# EffectsBox.net
KiCad netlist of a schematic drawn in EAGLE
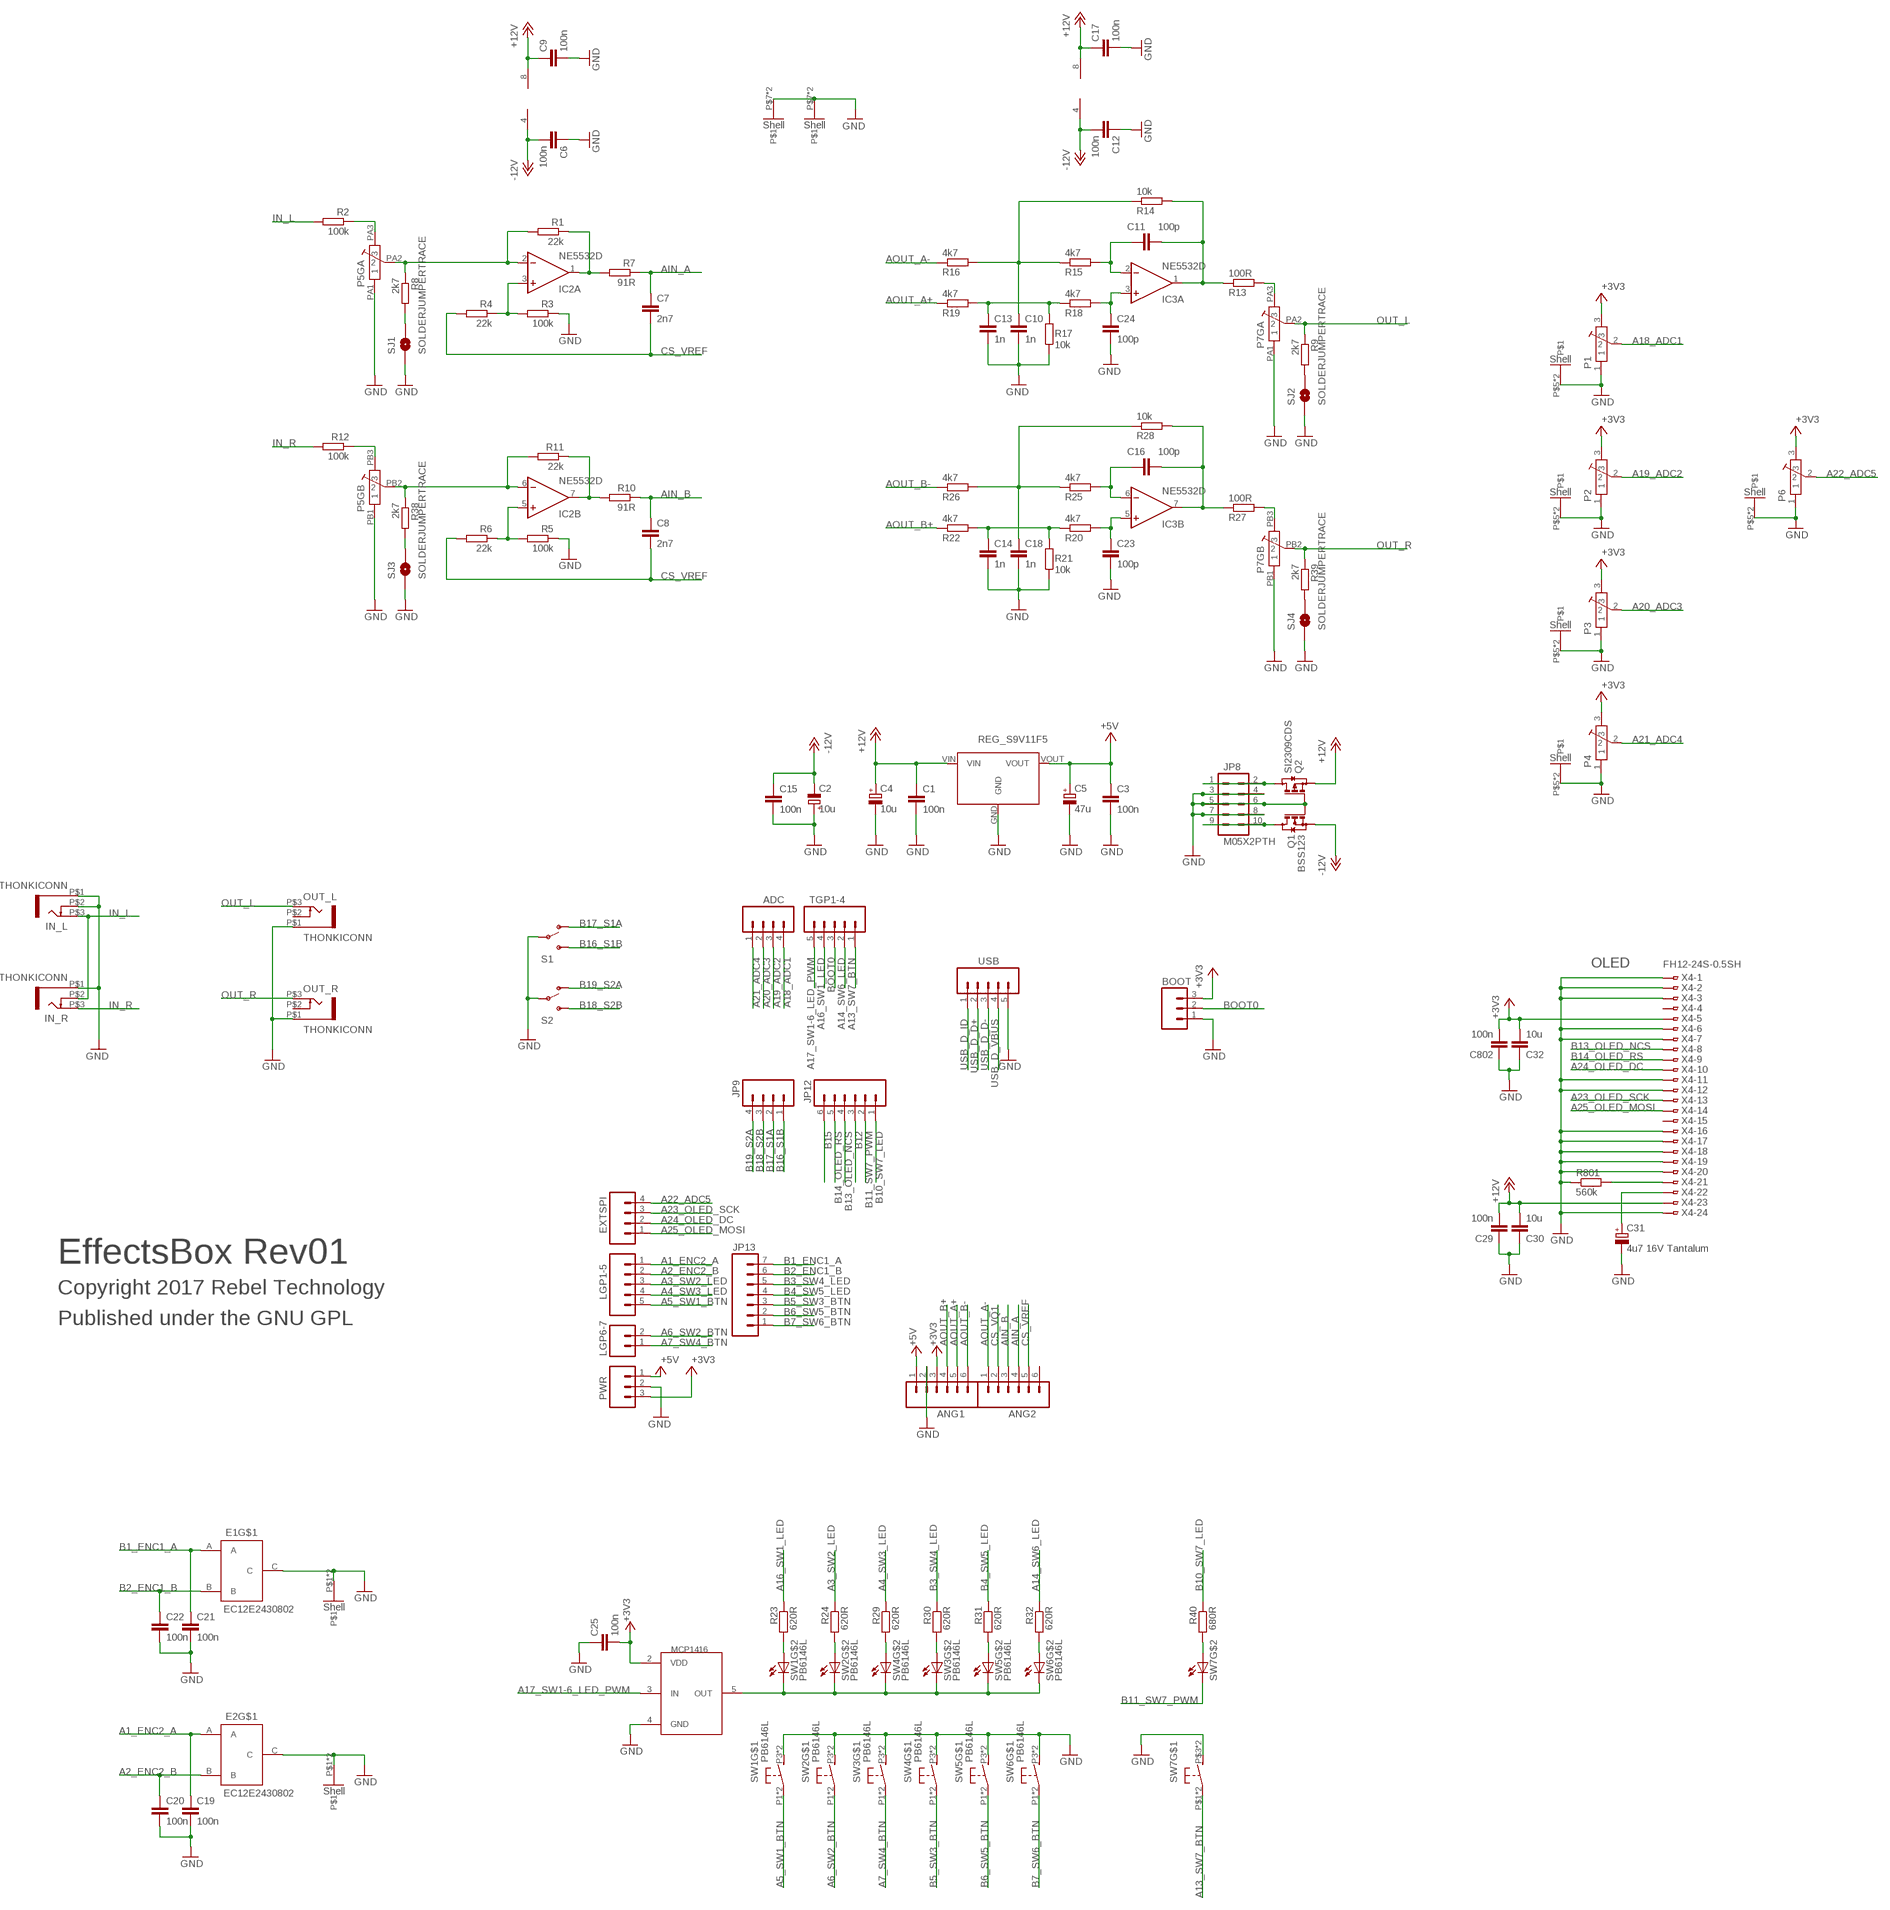
[diagram p0: schematic, sheet 1]

(export (version "E")
  (design (tool "Eeschema 10.0.6"))
  (components
    (comp (ref "ADC")
      (value "M04PTH")
      (footprint "eagle-import:1X04")
      (libsource (lib "eagle-import") (part "M04PTH"))
    )
    (comp (ref "ANG1")
      (value "M06SIP")
      (footprint "eagle-import:1X06")
      (libsource (lib "eagle-import") (part "M06SIP"))
    )
    (comp (ref "ANG2")
      (value "M06SIP")
      (footprint "eagle-import:1X06")
      (libsource (lib "eagle-import") (part "M06SIP"))
    )
    (comp (ref "BOOT")
      (value "M03PTH")
      (footprint "eagle-import:1X03")
      (libsource (lib "eagle-import") (part "M03PTH"))
    )
    (comp (ref "C1")
      (value "100n")
      (footprint "eagle-import:C0603")
      (libsource (lib "eagle-import") (part "C-EUC0603"))
    )
    (comp (ref "C2")
      (value "10u")
      (footprint "eagle-import:CPOL-5")
      (libsource (lib "eagle-import") (part "CPOL-EU153CLV-0505"))
    )
    (comp (ref "C3")
      (value "100n")
      (footprint "eagle-import:C0603")
      (libsource (lib "eagle-import") (part "C-EUC0603"))
    )
    (comp (ref "C4")
      (value "10u")
      (footprint "eagle-import:CPOL-5")
      (libsource (lib "eagle-import") (part "CPOL-EU153CLV-0505"))
    )
    (comp (ref "C5")
      (value "47u")
      (footprint "eagle-import:PANASONIC_C")
      (libsource (lib "eagle-import") (part "rcl_CPOL-EUC"))
    )
    (comp (ref "C6")
      (value "100n")
      (footprint "eagle-import:C0603")
      (libsource (lib "eagle-import") (part "resistor_C-EUC0603"))
    )
    (comp (ref "C7")
      (value "2n7")
      (footprint "eagle-import:C0603")
      (libsource (lib "eagle-import") (part "resistor_C-EUC0603"))
    )
    (comp (ref "C8")
      (value "2n7")
      (footprint "eagle-import:C0603")
      (libsource (lib "eagle-import") (part "resistor_C-EUC0603"))
    )
    (comp (ref "C9")
      (value "100n")
      (footprint "eagle-import:C0603")
      (libsource (lib "eagle-import") (part "resistor_C-EUC0603"))
    )
    (comp (ref "C10")
      (value "1n")
      (footprint "eagle-import:C0603")
      (libsource (lib "eagle-import") (part "resistor_C-EUC0603"))
    )
    (comp (ref "C11")
      (value "100p")
      (footprint "eagle-import:C0603")
      (libsource (lib "eagle-import") (part "resistor_C-EUC0603"))
    )
    (comp (ref "C12")
      (value "100n")
      (footprint "eagle-import:C0603")
      (libsource (lib "eagle-import") (part "resistor_C-EUC0603"))
    )
    (comp (ref "C13")
      (value "1n")
      (footprint "eagle-import:C0603")
      (libsource (lib "eagle-import") (part "resistor_C-EUC0603"))
    )
    (comp (ref "C14")
      (value "1n")
      (footprint "eagle-import:C0603")
      (libsource (lib "eagle-import") (part "resistor_C-EUC0603"))
    )
    (comp (ref "C15")
      (value "100n")
      (footprint "eagle-import:C0603")
      (libsource (lib "eagle-import") (part "C-EUC0603"))
    )
    (comp (ref "C16")
      (value "100p")
      (footprint "eagle-import:C0603")
      (libsource (lib "eagle-import") (part "resistor_C-EUC0603"))
    )
    (comp (ref "C17")
      (value "100n")
      (footprint "eagle-import:C0603")
      (libsource (lib "eagle-import") (part "resistor_C-EUC0603"))
    )
    (comp (ref "C18")
      (value "1n")
      (footprint "eagle-import:C0603")
      (libsource (lib "eagle-import") (part "resistor_C-EUC0603"))
    )
    (comp (ref "C19")
      (value "100n")
      (footprint "eagle-import:C0603")
      (libsource (lib "eagle-import") (part "C-EUC0603"))
    )
    (comp (ref "C20")
      (value "100n")
      (footprint "eagle-import:C0603")
      (libsource (lib "eagle-import") (part "C-EUC0603"))
    )
    (comp (ref "C21")
      (value "100n")
      (footprint "eagle-import:C0603")
      (libsource (lib "eagle-import") (part "C-EUC0603"))
    )
    (comp (ref "C22")
      (value "100n")
      (footprint "eagle-import:C0603")
      (libsource (lib "eagle-import") (part "C-EUC0603"))
    )
    (comp (ref "C23")
      (value "100p")
      (footprint "eagle-import:C0603")
      (libsource (lib "eagle-import") (part "resistor_C-EUC0603"))
    )
    (comp (ref "C24")
      (value "100p")
      (footprint "eagle-import:C0603")
      (libsource (lib "eagle-import") (part "resistor_C-EUC0603"))
    )
    (comp (ref "C25")
      (value "100n")
      (footprint "eagle-import:C0603")
      (libsource (lib "eagle-import") (part "C-EUC0603"))
    )
    (comp (ref "C29")
      (value "100n")
      (footprint "eagle-import:C0603")
      (libsource (lib "eagle-import") (part "C-EUC0603"))
    )
    (comp (ref "C30")
      (value "10u")
      (footprint "eagle-import:C1206")
      (libsource (lib "eagle-import") (part "C-EUC1206"))
    )
    (comp (ref "C31")
      (value "4u7 16V Tantalum")
      (footprint "eagle-import:SMC_A")
      (libsource (lib "eagle-import") (part "CPOL-EUSMCA"))
    )
    (comp (ref "C32")
      (value "10u")
      (footprint "eagle-import:C1206")
      (libsource (lib "eagle-import") (part "C-EUC1206"))
    )
    (comp (ref "C802")
      (value "100n")
      (footprint "eagle-import:C0603")
      (libsource (lib "eagle-import") (part "C-EUC0603"))
    )
    (comp (ref "E1")
      (value "EC12E2430802")
      (footprint "eagle-import:EC12E2430802")
      (libsource (lib "eagle-import") (part "EC12E2430802"))
    )
    (comp (ref "E2")
      (value "EC12E2430802")
      (footprint "eagle-import:EC12E2430802")
      (libsource (lib "eagle-import") (part "EC12E2430802"))
    )
    (comp (ref "EXTSPI")
      (value "M04PTH")
      (footprint "eagle-import:1X04")
      (libsource (lib "eagle-import") (part "M04PTH"))
    )
    (comp (ref "IC2")
      (value "NE5532D")
      (footprint "eagle-import:SO08")
      (libsource (lib "eagle-import") (part "NE5532D"))
    )
    (comp (ref "IC3")
      (value "NE5532D")
      (footprint "eagle-import:SO08")
      (libsource (lib "eagle-import") (part "NE5532D"))
    )
    (comp (ref "IN_L")
      (value "THONKICONN")
      (footprint "eagle-import:THONKICONN")
      (libsource (lib "eagle-import") (part "THONKICONN"))
    )
    (comp (ref "IN_R")
      (value "THONKICONN")
      (footprint "eagle-import:THONKICONN")
      (libsource (lib "eagle-import") (part "THONKICONN"))
    )
    (comp (ref "JP8")
      (value "M05X2PTH")
      (footprint "eagle-import:AVR_ICSP")
      (libsource (lib "eagle-import") (part "M05X2PTH"))
    )
    (comp (ref "JP9")
      (value "M04PTH")
      (footprint "eagle-import:1X04")
      (libsource (lib "eagle-import") (part "M04PTH"))
    )
    (comp (ref "JP12")
      (value "M06SIP")
      (footprint "eagle-import:1X06")
      (libsource (lib "eagle-import") (part "M06SIP"))
    )
    (comp (ref "JP13")
      (value "M07")
      (footprint "eagle-import:1X07")
      (libsource (lib "eagle-import") (part "M07"))
    )
    (comp (ref "LGP1-5")
      (value "M05PTH")
      (footprint "eagle-import:1X05")
      (libsource (lib "eagle-import") (part "M05PTH"))
    )
    (comp (ref "LGP6-7")
      (value "M02PTH")
      (footprint "eagle-import:1X02")
      (libsource (lib "eagle-import") (part "M02PTH"))
    )
    (comp (ref "OUT_L")
      (value "THONKICONN")
      (footprint "eagle-import:THONKICONN")
      (libsource (lib "eagle-import") (part "THONKICONN"))
    )
    (comp (ref "OUT_R")
      (value "THONKICONN")
      (footprint "eagle-import:THONKICONN")
      (libsource (lib "eagle-import") (part "THONKICONN"))
    )
    (comp (ref "P1")
      (value "POT-ALPS-RK09L1140")
      (footprint "eagle-import:POT-ALPS-RK09L1140")
      (libsource (lib "eagle-import") (part "POT-ALPS-RK09L1140"))
    )
    (comp (ref "P2")
      (value "POT-ALPS-RK09L1140")
      (footprint "eagle-import:POT-ALPS-RK09L1140")
      (libsource (lib "eagle-import") (part "POT-ALPS-RK09L1140"))
    )
    (comp (ref "P3")
      (value "POT-ALPS-RK09L1140")
      (footprint "eagle-import:POT-ALPS-RK09L1140")
      (libsource (lib "eagle-import") (part "POT-ALPS-RK09L1140"))
    )
    (comp (ref "P4")
      (value "POT-ALPS-RK09L1140")
      (footprint "eagle-import:POT-ALPS-RK09L1140")
      (libsource (lib "eagle-import") (part "POT-ALPS-RK09L1140"))
    )
    (comp (ref "P5")
      (value "POT-ALPS_RK09L12D0A1W")
      (footprint "eagle-import:POT-ALPS-RK09L12D0A1W")
      (libsource (lib "eagle-import") (part "POT-ALPS_RK09L12D0A1W"))
    )
    (comp (ref "P6")
      (value "POT-ALPS-RK09L1140")
      (footprint "eagle-import:POT-ALPS-RK09L1140")
      (libsource (lib "eagle-import") (part "POT-ALPS-RK09L1140"))
    )
    (comp (ref "P7")
      (value "POT-ALPS_RK09L12D0A1W")
      (footprint "eagle-import:POT-ALPS-RK09L12D0A1W")
      (libsource (lib "eagle-import") (part "POT-ALPS_RK09L12D0A1W"))
    )
    (comp (ref "PWR")
      (value "M03PTH")
      (footprint "eagle-import:1X03")
      (libsource (lib "eagle-import") (part "M03PTH"))
    )
    (comp (ref "Q1")
      (value "BSS123")
      (footprint "eagle-import:SOT23")
      (libsource (lib "eagle-import") (part "BSS123"))
    )
    (comp (ref "Q2")
      (value "SI2309CDS")
      (footprint "eagle-import:SOT23")
      (libsource (lib "eagle-import") (part "BSS84"))
    )
    (comp (ref "R1")
      (value "22k")
      (footprint "eagle-import:0603")
      (libsource (lib "eagle-import") (part "R-EU_0603"))
    )
    (comp (ref "R2")
      (value "100k")
      (footprint "eagle-import:0603")
      (libsource (lib "eagle-import") (part "R-EU_0603"))
    )
    (comp (ref "R3")
      (value "100k")
      (footprint "eagle-import:0603")
      (libsource (lib "eagle-import") (part "R-EU_0603"))
    )
    (comp (ref "R4")
      (value "22k")
      (footprint "eagle-import:0603")
      (libsource (lib "eagle-import") (part "R-EU_0603"))
    )
    (comp (ref "R5")
      (value "100k")
      (footprint "eagle-import:0603")
      (libsource (lib "eagle-import") (part "R-EU_0603"))
    )
    (comp (ref "R6")
      (value "22k")
      (footprint "eagle-import:0603")
      (libsource (lib "eagle-import") (part "R-EU_0603"))
    )
    (comp (ref "R7")
      (value "91R")
      (footprint "eagle-import:0603")
      (libsource (lib "eagle-import") (part "R-EU_0603"))
    )
    (comp (ref "R8")
      (value "2k7")
      (footprint "eagle-import:R0603")
      (libsource (lib "eagle-import") (part "R-EU_R0603"))
    )
    (comp (ref "R9")
      (value "2k7")
      (footprint "eagle-import:R0603")
      (libsource (lib "eagle-import") (part "R-EU_R0603"))
    )
    (comp (ref "R10")
      (value "91R")
      (footprint "eagle-import:0603")
      (libsource (lib "eagle-import") (part "R-EU_0603"))
    )
    (comp (ref "R11")
      (value "22k")
      (footprint "eagle-import:0603")
      (libsource (lib "eagle-import") (part "R-EU_0603"))
    )
    (comp (ref "R12")
      (value "100k")
      (footprint "eagle-import:0603")
      (libsource (lib "eagle-import") (part "R-EU_0603"))
    )
    (comp (ref "R13")
      (value "100R")
      (footprint "eagle-import:0603")
      (libsource (lib "eagle-import") (part "R-EU_0603"))
    )
    (comp (ref "R14")
      (value "10k")
      (footprint "eagle-import:0603")
      (libsource (lib "eagle-import") (part "R-EU_0603"))
    )
    (comp (ref "R15")
      (value "4k7")
      (footprint "eagle-import:0603")
      (libsource (lib "eagle-import") (part "R-EU_0603"))
    )
    (comp (ref "R16")
      (value "4k7")
      (footprint "eagle-import:0603")
      (libsource (lib "eagle-import") (part "R-EU_0603"))
    )
    (comp (ref "R17")
      (value "10k")
      (footprint "eagle-import:0603")
      (libsource (lib "eagle-import") (part "R-EU_0603"))
    )
    (comp (ref "R18")
      (value "4k7")
      (footprint "eagle-import:0603")
      (libsource (lib "eagle-import") (part "R-EU_0603"))
    )
    (comp (ref "R19")
      (value "4k7")
      (footprint "eagle-import:0603")
      (libsource (lib "eagle-import") (part "R-EU_0603"))
    )
    (comp (ref "R20")
      (value "4k7")
      (footprint "eagle-import:0603")
      (libsource (lib "eagle-import") (part "R-EU_0603"))
    )
    (comp (ref "R21")
      (value "10k")
      (footprint "eagle-import:0603")
      (libsource (lib "eagle-import") (part "R-EU_0603"))
    )
    (comp (ref "R22")
      (value "4k7")
      (footprint "eagle-import:0603")
      (libsource (lib "eagle-import") (part "R-EU_0603"))
    )
    (comp (ref "R23")
      (value "620R")
      (footprint "eagle-import:0603")
      (libsource (lib "eagle-import") (part "R-EU_0603"))
    )
    (comp (ref "R24")
      (value "620R")
      (footprint "eagle-import:0603")
      (libsource (lib "eagle-import") (part "R-EU_0603"))
    )
    (comp (ref "R25")
      (value "4k7")
      (footprint "eagle-import:0603")
      (libsource (lib "eagle-import") (part "R-EU_0603"))
    )
    (comp (ref "R26")
      (value "4k7")
      (footprint "eagle-import:0603")
      (libsource (lib "eagle-import") (part "R-EU_0603"))
    )
    (comp (ref "R27")
      (value "100R")
      (footprint "eagle-import:0603")
      (libsource (lib "eagle-import") (part "R-EU_0603"))
    )
    (comp (ref "R28")
      (value "10k")
      (footprint "eagle-import:0603")
      (libsource (lib "eagle-import") (part "R-EU_0603"))
    )
    (comp (ref "R29")
      (value "620R")
      (footprint "eagle-import:0603")
      (libsource (lib "eagle-import") (part "R-EU_0603"))
    )
    (comp (ref "R30")
      (value "620R")
      (footprint "eagle-import:0603")
      (libsource (lib "eagle-import") (part "R-EU_0603"))
    )
    (comp (ref "R31")
      (value "620R")
      (footprint "eagle-import:0603")
      (libsource (lib "eagle-import") (part "R-EU_0603"))
    )
    (comp (ref "R32")
      (value "620R")
      (footprint "eagle-import:0603")
      (libsource (lib "eagle-import") (part "R-EU_0603"))
    )
    (comp (ref "R38")
      (value "2k7")
      (footprint "eagle-import:R0603")
      (libsource (lib "eagle-import") (part "R-EU_R0603"))
    )
    (comp (ref "R39")
      (value "2k7")
      (footprint "eagle-import:R0603")
      (libsource (lib "eagle-import") (part "R-EU_R0603"))
    )
    (comp (ref "R40")
      (value "680R")
      (footprint "eagle-import:0603")
      (libsource (lib "eagle-import") (part "R-EU_0603"))
    )
    (comp (ref "R801")
      (value "560k")
      (footprint "eagle-import:0603")
      (libsource (lib "eagle-import") (part "R-EU_0603"))
    )
    (comp (ref "S1")
      (value "SWITCH-SPST")
      (footprint "eagle-import:SWITCH-SPDT-SALECOM-T8014")
      (libsource (lib "eagle-import") (part "SWITCH-SPST"))
    )
    (comp (ref "S2")
      (value "SWITCH-SPST")
      (footprint "eagle-import:SWITCH-SPDT-SALECOM-T8014")
      (libsource (lib "eagle-import") (part "SWITCH-SPST"))
    )
    (comp (ref "SJ1")
      (value "SOLDERJUMPERTRACE")
      (footprint "eagle-import:SJ_2S-TRACE")
      (libsource (lib "eagle-import") (part "SOLDERJUMPERTRACE"))
    )
    (comp (ref "SJ2")
      (value "SOLDERJUMPERTRACE")
      (footprint "eagle-import:SJ_2S-TRACE")
      (libsource (lib "eagle-import") (part "SOLDERJUMPERTRACE"))
    )
    (comp (ref "SJ3")
      (value "SOLDERJUMPERTRACE")
      (footprint "eagle-import:SJ_2S-TRACE")
      (libsource (lib "eagle-import") (part "SOLDERJUMPERTRACE"))
    )
    (comp (ref "SJ4")
      (value "SOLDERJUMPERTRACE")
      (footprint "eagle-import:SJ_2S-TRACE")
      (libsource (lib "eagle-import") (part "SOLDERJUMPERTRACE"))
    )
    (comp (ref "SW1")
      (value "PB6146L")
      (footprint "eagle-import:PB6146L")
      (libsource (lib "eagle-import") (part "PB6146L"))
    )
    (comp (ref "SW2")
      (value "PB6146L")
      (footprint "eagle-import:PB6146L")
      (libsource (lib "eagle-import") (part "PB6146L"))
    )
    (comp (ref "SW3")
      (value "PB6146L")
      (footprint "eagle-import:PB6146L")
      (libsource (lib "eagle-import") (part "PB6146L"))
    )
    (comp (ref "SW4")
      (value "PB6146L")
      (footprint "eagle-import:PB6146L")
      (libsource (lib "eagle-import") (part "PB6146L"))
    )
    (comp (ref "SW5")
      (value "PB6146L")
      (footprint "eagle-import:PB6146L")
      (libsource (lib "eagle-import") (part "PB6146L"))
    )
    (comp (ref "SW6")
      (value "PB6146L")
      (footprint "eagle-import:PB6146L")
      (libsource (lib "eagle-import") (part "PB6146L"))
    )
    (comp (ref "SW7")
      (value "KS01-BL")
      (footprint "eagle-import:KS01-BL")
      (libsource (lib "eagle-import") (part "KS01-BL"))
    )
    (comp (ref "TGP1-4")
      (value "M05PTH")
      (footprint "eagle-import:1X05")
      (libsource (lib "eagle-import") (part "M05PTH"))
    )
    (comp (ref "U1")
      (value "REG_S9V11F5")
      (footprint "eagle-import:REG_S9V11F5")
      (libsource (lib "eagle-import") (part "REG_S9V11F5"))
    )
    (comp (ref "U2")
      (value "MCP1416")
      (footprint "eagle-import:SOT23-5")
      (libsource (lib "eagle-import") (part "MCP1416"))
    )
    (comp (ref "USB")
      (value "M05PTH")
      (footprint "eagle-import:1X05")
      (libsource (lib "eagle-import") (part "M05PTH"))
    )
    (comp (ref "X4")
      (value "FH12-24S-0.5SH")
      (footprint "eagle-import:FH12-24S-0.5SH")
      (fields (field (name "MPN") "FH12-24S-0.5SH(55)"))
      (libsource (lib "eagle-import") (part "FH12-24S-0.5SH"))
    )
  )
  (nets
    (net (code "1") (name "+3V3") (class "Default")
      (node (ref "ANG1") (pin "3") (pinfunction "3_3") (pintype "passive"))
      (node (ref "BOOT") (pin "3") (pinfunction "3_3") (pintype "passive"))
      (node (ref "C25") (pin "2") (pinfunction "2_2") (pintype "passive"))
      (node (ref "C32") (pin "2") (pinfunction "2_2") (pintype "passive"))
      (node (ref "C802") (pin "2") (pinfunction "2_2") (pintype "passive"))
      (node (ref "P1") (pin "3") (pinfunction "3_3") (pintype "bidirectional"))
      (node (ref "P2") (pin "3") (pinfunction "3_3") (pintype "bidirectional"))
      (node (ref "P3") (pin "3") (pinfunction "3_3") (pintype "bidirectional"))
      (node (ref "P4") (pin "3") (pinfunction "3_3") (pintype "bidirectional"))
      (node (ref "P6") (pin "3") (pinfunction "3_3") (pintype "bidirectional"))
      (node (ref "PWR") (pin "3") (pinfunction "3_3") (pintype "passive"))
      (node (ref "U2") (pin "2") (pinfunction "VDD_2") (pintype "bidirectional"))
      (node (ref "X4") (pin "5") (pinfunction "1_5") (pintype "passive"))
    )
    (net (code "2") (name "+5V") (class "Default")
      (node (ref "ANG1") (pin "1") (pinfunction "1_1") (pintype "passive"))
      (node (ref "C3") (pin "1") (pinfunction "1_1") (pintype "passive"))
      (node (ref "C5") (pin "+") (pinfunction "+_+") (pintype "passive"))
      (node (ref "PWR") (pin "1") (pinfunction "1_1") (pintype "passive"))
      (node (ref "U1") (pin "VOUT") (pinfunction "VOUT_VOUT") (pintype "output"))
    )
    (net (code "3") (name "+12V") (class "Default")
      (node (ref "C1") (pin "1") (pinfunction "1_1") (pintype "passive"))
      (node (ref "C17") (pin "1") (pinfunction "1_1") (pintype "passive"))
      (node (ref "C29") (pin "2") (pinfunction "2_2") (pintype "passive"))
      (node (ref "C30") (pin "2") (pinfunction "2_2") (pintype "passive"))
      (node (ref "C4") (pin "+") (pinfunction "+_+") (pintype "passive"))
      (node (ref "C9") (pin "1") (pinfunction "1_1") (pintype "passive"))
      (node (ref "IC2") (pin "8") (pinfunction "V+_8") (pintype "power_in"))
      (node (ref "IC3") (pin "8") (pinfunction "V+_8") (pintype "power_in"))
      (node (ref "Q2") (pin "2") (pinfunction "S_2") (pintype "passive"))
      (node (ref "U1") (pin "VIN") (pinfunction "VIN_VIN") (pintype "input"))
      (node (ref "X4") (pin "23") (pinfunction "1_23") (pintype "passive"))
    )
    (net (code "4") (name "-12V") (class "Default")
      (node (ref "C12") (pin "2") (pinfunction "2_2") (pintype "passive"))
      (node (ref "C15") (pin "1") (pinfunction "1_1") (pintype "passive"))
      (node (ref "C2") (pin "-") (pinfunction "-_-") (pintype "passive"))
      (node (ref "C6") (pin "2") (pinfunction "2_2") (pintype "passive"))
      (node (ref "IC2") (pin "4") (pinfunction "V-_4") (pintype "power_in"))
      (node (ref "IC3") (pin "4") (pinfunction "V-_4") (pintype "power_in"))
      (node (ref "Q1") (pin "2") (pinfunction "S_2") (pintype "passive"))
    )
    (net (code "5") (name "/A1_ENC2_A") (class "Default")
      (node (ref "C19") (pin "1") (pinfunction "1_1") (pintype "passive"))
      (node (ref "E2") (pin "A") (pinfunction "A_A") (pintype "bidirectional"))
      (node (ref "LGP1-5") (pin "1") (pinfunction "1_1") (pintype "passive"))
    )
    (net (code "6") (name "/A2_ENC2_B") (class "Default")
      (node (ref "C20") (pin "1") (pinfunction "1_1") (pintype "passive"))
      (node (ref "E2") (pin "B") (pinfunction "B_B") (pintype "bidirectional"))
      (node (ref "LGP1-5") (pin "2") (pinfunction "2_2") (pintype "passive"))
    )
    (net (code "7") (name "/A3_SW2_LED") (class "Default")
      (node (ref "LGP1-5") (pin "3") (pinfunction "3_3") (pintype "passive"))
      (node (ref "R24") (pin "1") (pinfunction "1_1") (pintype "passive"))
    )
    (net (code "8") (name "/A4_SW3_LED") (class "Default")
      (node (ref "LGP1-5") (pin "4") (pinfunction "4_4") (pintype "passive"))
      (node (ref "R29") (pin "1") (pinfunction "1_1") (pintype "passive"))
    )
    (net (code "9") (name "/A5_SW1_BTN") (class "Default")
      (node (ref "LGP1-5") (pin "5") (pinfunction "5_5") (pintype "passive"))
      (node (ref "SW1") (pin "P1") (pinfunction "P_P1") (pintype "passive"))
      (node (ref "SW1") (pin "P2") (pinfunction "P_P2") (pintype "passive"))
    )
    (net (code "10") (name "/A6_SW2_BTN") (class "Default")
      (node (ref "LGP6-7") (pin "2") (pinfunction "2_2") (pintype "passive"))
      (node (ref "SW2") (pin "P1") (pinfunction "P_P1") (pintype "passive"))
      (node (ref "SW2") (pin "P2") (pinfunction "P_P2") (pintype "passive"))
    )
    (net (code "11") (name "/A7_SW4_BTN") (class "Default")
      (node (ref "LGP6-7") (pin "1") (pinfunction "1_1") (pintype "passive"))
      (node (ref "SW3") (pin "P1") (pinfunction "P_P1") (pintype "passive"))
      (node (ref "SW3") (pin "P2") (pinfunction "P_P2") (pintype "passive"))
    )
    (net (code "12") (name "/A13_SW7_BTN") (class "Default")
      (node (ref "SW7") (pin "P$1") (pinfunction "P_P$1") (pintype "passive"))
      (node (ref "SW7") (pin "P$2") (pinfunction "P_P$2") (pintype "passive"))
      (node (ref "TGP1-4") (pin "1") (pinfunction "1_1") (pintype "passive"))
    )
    (net (code "13") (name "/A14_SW6_LED") (class "Default")
      (node (ref "R32") (pin "1") (pinfunction "1_1") (pintype "passive"))
      (node (ref "TGP1-4") (pin "2") (pinfunction "2_2") (pintype "passive"))
    )
    (net (code "14") (name "/A16_SW1_LED") (class "Default")
      (node (ref "R23") (pin "1") (pinfunction "1_1") (pintype "passive"))
      (node (ref "TGP1-4") (pin "4") (pinfunction "4_4") (pintype "passive"))
    )
    (net (code "15") (name "/A17_SW1-6_LED_PWM") (class "Default")
      (node (ref "TGP1-4") (pin "5") (pinfunction "5_5") (pintype "passive"))
      (node (ref "U2") (pin "3") (pinfunction "IN_3") (pintype "bidirectional"))
    )
    (net (code "16") (name "/A18_ADC1") (class "Default")
      (node (ref "ADC") (pin "4") (pinfunction "4_4") (pintype "passive"))
      (node (ref "P1") (pin "2") (pinfunction "2_2") (pintype "bidirectional"))
    )
    (net (code "17") (name "/A19_ADC2") (class "Default")
      (node (ref "ADC") (pin "3") (pinfunction "3_3") (pintype "passive"))
      (node (ref "P2") (pin "2") (pinfunction "2_2") (pintype "bidirectional"))
    )
    (net (code "18") (name "/A20_ADC3") (class "Default")
      (node (ref "ADC") (pin "2") (pinfunction "2_2") (pintype "passive"))
      (node (ref "P3") (pin "2") (pinfunction "2_2") (pintype "bidirectional"))
    )
    (net (code "19") (name "/A21_ADC4") (class "Default")
      (node (ref "ADC") (pin "1") (pinfunction "1_1") (pintype "passive"))
      (node (ref "P4") (pin "2") (pinfunction "2_2") (pintype "bidirectional"))
    )
    (net (code "20") (name "/A22_ADC5") (class "Default")
      (node (ref "EXTSPI") (pin "4") (pinfunction "4_4") (pintype "passive"))
      (node (ref "P6") (pin "2") (pinfunction "2_2") (pintype "bidirectional"))
    )
    (net (code "21") (name "/A23_OLED_SCK") (class "Default")
      (node (ref "EXTSPI") (pin "3") (pinfunction "3_3") (pintype "passive"))
      (node (ref "X4") (pin "13") (pinfunction "1_13") (pintype "passive"))
    )
    (net (code "22") (name "/A24_OLED_DC") (class "Default")
      (node (ref "EXTSPI") (pin "2") (pinfunction "2_2") (pintype "passive"))
      (node (ref "X4") (pin "10") (pinfunction "1_10") (pintype "passive"))
    )
    (net (code "23") (name "/A25_OLED_MOSI") (class "Default")
      (node (ref "EXTSPI") (pin "1") (pinfunction "1_1") (pintype "passive"))
      (node (ref "X4") (pin "14") (pinfunction "1_14") (pintype "passive"))
    )
    (net (code "24") (name "/AIN_A") (class "Default")
      (node (ref "ANG2") (pin "4") (pinfunction "4_4") (pintype "passive"))
      (node (ref "C7") (pin "1") (pinfunction "1_1") (pintype "passive"))
      (node (ref "R7") (pin "1") (pinfunction "1_1") (pintype "passive"))
    )
    (net (code "25") (name "/AIN_B") (class "Default")
      (node (ref "ANG2") (pin "3") (pinfunction "3_3") (pintype "passive"))
      (node (ref "C8") (pin "1") (pinfunction "1_1") (pintype "passive"))
      (node (ref "R10") (pin "1") (pinfunction "1_1") (pintype "passive"))
    )
    (net (code "26") (name "/AOUT_A+") (class "Default")
      (node (ref "ANG1") (pin "5") (pinfunction "5_5") (pintype "passive"))
      (node (ref "R19") (pin "1") (pinfunction "1_1") (pintype "passive"))
    )
    (net (code "27") (name "/AOUT_A-") (class "Default")
      (node (ref "ANG2") (pin "1") (pinfunction "1_1") (pintype "passive"))
      (node (ref "R16") (pin "1") (pinfunction "1_1") (pintype "passive"))
    )
    (net (code "28") (name "/AOUT_B+") (class "Default")
      (node (ref "ANG1") (pin "4") (pinfunction "4_4") (pintype "passive"))
      (node (ref "R22") (pin "1") (pinfunction "1_1") (pintype "passive"))
    )
    (net (code "29") (name "/AOUT_B-") (class "Default")
      (node (ref "ANG1") (pin "6") (pinfunction "6_6") (pintype "passive"))
      (node (ref "R26") (pin "1") (pinfunction "1_1") (pintype "passive"))
    )
    (net (code "30") (name "/B1_ENC1_A") (class "Default")
      (node (ref "C21") (pin "1") (pinfunction "1_1") (pintype "passive"))
      (node (ref "E1") (pin "A") (pinfunction "A_A") (pintype "bidirectional"))
      (node (ref "JP13") (pin "7") (pinfunction "7_7") (pintype "passive"))
    )
    (net (code "31") (name "/B2_ENC1_B") (class "Default")
      (node (ref "C22") (pin "1") (pinfunction "1_1") (pintype "passive"))
      (node (ref "E1") (pin "B") (pinfunction "B_B") (pintype "bidirectional"))
      (node (ref "JP13") (pin "6") (pinfunction "6_6") (pintype "passive"))
    )
    (net (code "32") (name "/B3_SW4_LED") (class "Default")
      (node (ref "JP13") (pin "5") (pinfunction "5_5") (pintype "passive"))
      (node (ref "R30") (pin "1") (pinfunction "1_1") (pintype "passive"))
    )
    (net (code "33") (name "/B4_SW5_LED") (class "Default")
      (node (ref "JP13") (pin "4") (pinfunction "4_4") (pintype "passive"))
      (node (ref "R31") (pin "1") (pinfunction "1_1") (pintype "passive"))
    )
    (net (code "34") (name "/B5_SW3_BTN") (class "Default")
      (node (ref "JP13") (pin "3") (pinfunction "3_3") (pintype "passive"))
      (node (ref "SW4") (pin "P1") (pinfunction "P_P1") (pintype "passive"))
      (node (ref "SW4") (pin "P2") (pinfunction "P_P2") (pintype "passive"))
    )
    (net (code "35") (name "/B6_SW5_BTN") (class "Default")
      (node (ref "JP13") (pin "2") (pinfunction "2_2") (pintype "passive"))
      (node (ref "SW5") (pin "P1") (pinfunction "P_P1") (pintype "passive"))
      (node (ref "SW5") (pin "P2") (pinfunction "P_P2") (pintype "passive"))
    )
    (net (code "36") (name "/B7_SW6_BTN") (class "Default")
      (node (ref "JP13") (pin "1") (pinfunction "1_1") (pintype "passive"))
      (node (ref "SW6") (pin "P1") (pinfunction "P_P1") (pintype "passive"))
      (node (ref "SW6") (pin "P2") (pinfunction "P_P2") (pintype "passive"))
    )
    (net (code "37") (name "/B10_SW7_LED") (class "Default")
      (node (ref "JP12") (pin "1") (pinfunction "1_1") (pintype "passive"))
      (node (ref "R40") (pin "1") (pinfunction "1_1") (pintype "passive"))
    )
    (net (code "38") (name "/B11_SW7_PWM") (class "Default")
      (node (ref "JP12") (pin "2") (pinfunction "2_2") (pintype "passive"))
      (node (ref "SW7") (pin "P$C") (pinfunction "C_P$C") (pintype "passive"))
    )
    (net (code "39") (name "/B12") (class "Default")
      (node (ref "JP12") (pin "3") (pinfunction "3_3") (pintype "passive"))
    )
    (net (code "40") (name "/B13_OLED_NCS") (class "Default")
      (node (ref "JP12") (pin "4") (pinfunction "4_4") (pintype "passive"))
      (node (ref "X4") (pin "8") (pinfunction "1_8") (pintype "passive"))
    )
    (net (code "41") (name "/B14_OLED_RS") (class "Default")
      (node (ref "JP12") (pin "5") (pinfunction "5_5") (pintype "passive"))
      (node (ref "X4") (pin "9") (pinfunction "1_9") (pintype "passive"))
    )
    (net (code "42") (name "/B15") (class "Default")
      (node (ref "JP12") (pin "6") (pinfunction "6_6") (pintype "passive"))
    )
    (net (code "43") (name "/B16_S1B") (class "Default")
      (node (ref "JP9") (pin "1") (pinfunction "1_1") (pintype "passive"))
      (node (ref "S1") (pin "3") (pinfunction "S_3") (pintype "passive"))
    )
    (net (code "44") (name "/B17_S1A") (class "Default")
      (node (ref "JP9") (pin "2") (pinfunction "2_2") (pintype "passive"))
      (node (ref "S1") (pin "1") (pinfunction "O_1") (pintype "passive"))
    )
    (net (code "45") (name "/B18_S2B") (class "Default")
      (node (ref "JP9") (pin "3") (pinfunction "3_3") (pintype "passive"))
      (node (ref "S2") (pin "3") (pinfunction "S_3") (pintype "passive"))
    )
    (net (code "46") (name "/B19_S2A") (class "Default")
      (node (ref "JP9") (pin "4") (pinfunction "4_4") (pintype "passive"))
      (node (ref "S2") (pin "1") (pinfunction "O_1") (pintype "passive"))
    )
    (net (code "47") (name "/BOOT0") (class "Default")
      (node (ref "BOOT") (pin "2") (pinfunction "2_2") (pintype "passive"))
      (node (ref "TGP1-4") (pin "3") (pinfunction "3_3") (pintype "passive"))
    )
    (net (code "48") (name "/CS_VQ1") (class "Default")
      (node (ref "ANG2") (pin "2") (pinfunction "2_2") (pintype "passive"))
    )
    (net (code "49") (name "/CS_VREF") (class "Default")
      (node (ref "ANG2") (pin "5") (pinfunction "5_5") (pintype "passive"))
      (node (ref "C7") (pin "2") (pinfunction "2_2") (pintype "passive"))
      (node (ref "C8") (pin "2") (pinfunction "2_2") (pintype "passive"))
      (node (ref "R4") (pin "2") (pinfunction "2_2") (pintype "passive"))
      (node (ref "R6") (pin "2") (pinfunction "2_2") (pintype "passive"))
    )
    (net (code "50") (name "/IN_L") (class "Default")
      (node (ref "IN_L") (pin "P$3") (pinfunction "3_P$3") (pintype "passive"))
      (node (ref "IN_R") (pin "P$2") (pinfunction "4_P$2") (pintype "passive"))
      (node (ref "R2") (pin "2") (pinfunction "2_2") (pintype "passive"))
    )
    (net (code "51") (name "/IN_R") (class "Default")
      (node (ref "IN_R") (pin "P$3") (pinfunction "3_P$3") (pintype "passive"))
      (node (ref "R12") (pin "2") (pinfunction "2_2") (pintype "passive"))
    )
    (net (code "52") (name "/OUT_L") (class "Default")
      (node (ref "OUT_L") (pin "P$3") (pinfunction "3_P$3") (pintype "passive"))
      (node (ref "P7") (pin "PA2") (pinfunction "2_PA2") (pintype "bidirectional"))
      (node (ref "R9") (pin "1") (pinfunction "1_1") (pintype "passive"))
    )
    (net (code "53") (name "/OUT_R") (class "Default")
      (node (ref "OUT_R") (pin "P$3") (pinfunction "3_P$3") (pintype "passive"))
      (node (ref "P7") (pin "PB2") (pinfunction "2_PB2") (pintype "bidirectional"))
      (node (ref "R39") (pin "1") (pinfunction "1_1") (pintype "passive"))
    )
    (net (code "54") (name "/USB_D_D+") (class "Default")
      (node (ref "USB") (pin "2") (pinfunction "2_2") (pintype "passive"))
    )
    (net (code "55") (name "/USB_D_D-") (class "Default")
      (node (ref "USB") (pin "3") (pinfunction "3_3") (pintype "passive"))
    )
    (net (code "56") (name "/USB_D_ID") (class "Default")
      (node (ref "USB") (pin "1") (pinfunction "1_1") (pintype "passive"))
    )
    (net (code "57") (name "/USB_D_VBUS") (class "Default")
      (node (ref "USB") (pin "4") (pinfunction "4_4") (pintype "passive"))
    )
    (net (code "58") (name "GND") (class "Default")
      (node (ref "ANG1") (pin "2") (pinfunction "2_2") (pintype "passive"))
      (node (ref "BOOT") (pin "1") (pinfunction "1_1") (pintype "passive"))
      (node (ref "C1") (pin "2") (pinfunction "2_2") (pintype "passive"))
      (node (ref "C10") (pin "2") (pinfunction "2_2") (pintype "passive"))
      (node (ref "C12") (pin "1") (pinfunction "1_1") (pintype "passive"))
      (node (ref "C13") (pin "2") (pinfunction "2_2") (pintype "passive"))
      (node (ref "C14") (pin "2") (pinfunction "2_2") (pintype "passive"))
      (node (ref "C15") (pin "2") (pinfunction "2_2") (pintype "passive"))
      (node (ref "C17") (pin "2") (pinfunction "2_2") (pintype "passive"))
      (node (ref "C18") (pin "2") (pinfunction "2_2") (pintype "passive"))
      (node (ref "C19") (pin "2") (pinfunction "2_2") (pintype "passive"))
      (node (ref "C2") (pin "+") (pinfunction "+_+") (pintype "passive"))
      (node (ref "C20") (pin "2") (pinfunction "2_2") (pintype "passive"))
      (node (ref "C21") (pin "2") (pinfunction "2_2") (pintype "passive"))
      (node (ref "C22") (pin "2") (pinfunction "2_2") (pintype "passive"))
      (node (ref "C23") (pin "1") (pinfunction "1_1") (pintype "passive"))
      (node (ref "C24") (pin "1") (pinfunction "1_1") (pintype "passive"))
      (node (ref "C25") (pin "1") (pinfunction "1_1") (pintype "passive"))
      (node (ref "C29") (pin "1") (pinfunction "1_1") (pintype "passive"))
      (node (ref "C3") (pin "2") (pinfunction "2_2") (pintype "passive"))
      (node (ref "C30") (pin "1") (pinfunction "1_1") (pintype "passive"))
      (node (ref "C31") (pin "-") (pinfunction "-_-") (pintype "passive"))
      (node (ref "C32") (pin "1") (pinfunction "1_1") (pintype "passive"))
      (node (ref "C4") (pin "-") (pinfunction "-_-") (pintype "passive"))
      (node (ref "C5") (pin "-") (pinfunction "-_-") (pintype "passive"))
      (node (ref "C6") (pin "1") (pinfunction "1_1") (pintype "passive"))
      (node (ref "C802") (pin "1") (pinfunction "1_1") (pintype "passive"))
      (node (ref "C9") (pin "2") (pinfunction "2_2") (pintype "passive"))
      (node (ref "E1") (pin "C") (pinfunction "C_C") (pintype "bidirectional"))
      (node (ref "E1") (pin "P$1") (pinfunction "P$1_P$1") (pintype "bidirectional"))
      (node (ref "E1") (pin "P$2") (pinfunction "P$1_P$2") (pintype "bidirectional"))
      (node (ref "E2") (pin "C") (pinfunction "C_C") (pintype "bidirectional"))
      (node (ref "E2") (pin "P$1") (pinfunction "P$1_P$1") (pintype "bidirectional"))
      (node (ref "E2") (pin "P$2") (pinfunction "P$1_P$2") (pintype "bidirectional"))
      (node (ref "IN_L") (pin "P$1") (pinfunction "5_P$1") (pintype "passive"))
      (node (ref "IN_L") (pin "P$2") (pinfunction "4_P$2") (pintype "passive"))
      (node (ref "IN_R") (pin "P$1") (pinfunction "5_P$1") (pintype "passive"))
      (node (ref "JP8") (pin "3") (pinfunction "3_3") (pintype "passive"))
      (node (ref "JP8") (pin "4") (pinfunction "4_4") (pintype "passive"))
      (node (ref "JP8") (pin "5") (pinfunction "5_5") (pintype "passive"))
      (node (ref "JP8") (pin "6") (pinfunction "6_6") (pintype "passive"))
      (node (ref "JP8") (pin "7") (pinfunction "7_7") (pintype "passive"))
      (node (ref "JP8") (pin "8") (pinfunction "8_8") (pintype "passive"))
      (node (ref "OUT_L") (pin "P$1") (pinfunction "5_P$1") (pintype "passive"))
      (node (ref "OUT_R") (pin "P$1") (pinfunction "5_P$1") (pintype "passive"))
      (node (ref "P1") (pin "1") (pinfunction "1_1") (pintype "bidirectional"))
      (node (ref "P1") (pin "P$5") (pinfunction "P$1_P$5") (pintype "bidirectional"))
      (node (ref "P1") (pin "P$6") (pinfunction "P$1_P$6") (pintype "bidirectional"))
      (node (ref "P2") (pin "1") (pinfunction "1_1") (pintype "bidirectional"))
      (node (ref "P2") (pin "P$5") (pinfunction "P$1_P$5") (pintype "bidirectional"))
      (node (ref "P2") (pin "P$6") (pinfunction "P$1_P$6") (pintype "bidirectional"))
      (node (ref "P3") (pin "1") (pinfunction "1_1") (pintype "bidirectional"))
      (node (ref "P3") (pin "P$5") (pinfunction "P$1_P$5") (pintype "bidirectional"))
      (node (ref "P3") (pin "P$6") (pinfunction "P$1_P$6") (pintype "bidirectional"))
      (node (ref "P4") (pin "1") (pinfunction "1_1") (pintype "bidirectional"))
      (node (ref "P4") (pin "P$5") (pinfunction "P$1_P$5") (pintype "bidirectional"))
      (node (ref "P4") (pin "P$6") (pinfunction "P$1_P$6") (pintype "bidirectional"))
      (node (ref "P5") (pin "P$7") (pinfunction "P$1_P$7") (pintype "bidirectional"))
      (node (ref "P5") (pin "P$8") (pinfunction "P$1_P$8") (pintype "bidirectional"))
      (node (ref "P5") (pin "PA1") (pinfunction "1_PA1") (pintype "bidirectional"))
      (node (ref "P5") (pin "PB1") (pinfunction "1_PB1") (pintype "bidirectional"))
      (node (ref "P6") (pin "1") (pinfunction "1_1") (pintype "bidirectional"))
      (node (ref "P6") (pin "P$5") (pinfunction "P$1_P$5") (pintype "bidirectional"))
      (node (ref "P6") (pin "P$6") (pinfunction "P$1_P$6") (pintype "bidirectional"))
      (node (ref "P7") (pin "P$7") (pinfunction "P$1_P$7") (pintype "bidirectional"))
      (node (ref "P7") (pin "P$8") (pinfunction "P$1_P$8") (pintype "bidirectional"))
      (node (ref "P7") (pin "PA1") (pinfunction "1_PA1") (pintype "bidirectional"))
      (node (ref "P7") (pin "PB1") (pinfunction "1_PB1") (pintype "bidirectional"))
      (node (ref "PWR") (pin "2") (pinfunction "2_2") (pintype "passive"))
      (node (ref "Q1") (pin "1") (pinfunction "G_1") (pintype "passive"))
      (node (ref "Q2") (pin "1") (pinfunction "G_1") (pintype "passive"))
      (node (ref "R17") (pin "1") (pinfunction "1_1") (pintype "passive"))
      (node (ref "R21") (pin "1") (pinfunction "1_1") (pintype "passive"))
      (node (ref "R3") (pin "1") (pinfunction "1_1") (pintype "passive"))
      (node (ref "R5") (pin "1") (pinfunction "1_1") (pintype "passive"))
      (node (ref "R801") (pin "1") (pinfunction "1_1") (pintype "passive"))
      (node (ref "S1") (pin "2") (pinfunction "P_2") (pintype "passive"))
      (node (ref "S2") (pin "2") (pinfunction "P_2") (pintype "passive"))
      (node (ref "SJ1") (pin "1") (pinfunction "1_1") (pintype "passive"))
      (node (ref "SJ2") (pin "1") (pinfunction "1_1") (pintype "passive"))
      (node (ref "SJ3") (pin "1") (pinfunction "1_1") (pintype "passive"))
      (node (ref "SJ4") (pin "1") (pinfunction "1_1") (pintype "passive"))
      (node (ref "SW1") (pin "P3") (pinfunction "S_P3") (pintype "passive"))
      (node (ref "SW1") (pin "P4") (pinfunction "S_P4") (pintype "passive"))
      (node (ref "SW2") (pin "P3") (pinfunction "S_P3") (pintype "passive"))
      (node (ref "SW2") (pin "P4") (pinfunction "S_P4") (pintype "passive"))
      (node (ref "SW3") (pin "P3") (pinfunction "S_P3") (pintype "passive"))
      (node (ref "SW3") (pin "P4") (pinfunction "S_P4") (pintype "passive"))
      (node (ref "SW4") (pin "P3") (pinfunction "S_P3") (pintype "passive"))
      (node (ref "SW4") (pin "P4") (pinfunction "S_P4") (pintype "passive"))
      (node (ref "SW5") (pin "P3") (pinfunction "S_P3") (pintype "passive"))
      (node (ref "SW5") (pin "P4") (pinfunction "S_P4") (pintype "passive"))
      (node (ref "SW6") (pin "P3") (pinfunction "S_P3") (pintype "passive"))
      (node (ref "SW6") (pin "P4") (pinfunction "S_P4") (pintype "passive"))
      (node (ref "SW7") (pin "P$3") (pinfunction "S_P$3") (pintype "passive"))
      (node (ref "SW7") (pin "P$4") (pinfunction "S_P$4") (pintype "passive"))
      (node (ref "U1") (pin "GND") (pinfunction "GND_GND") (pintype "power_in"))
      (node (ref "U2") (pin "4") (pinfunction "GND_4") (pintype "bidirectional"))
      (node (ref "USB") (pin "5") (pinfunction "5_5") (pintype "passive"))
      (node (ref "X4") (pin "1") (pinfunction "1_1") (pintype "passive"))
      (node (ref "X4") (pin "11") (pinfunction "1_11") (pintype "passive"))
      (node (ref "X4") (pin "12") (pinfunction "1_12") (pintype "passive"))
      (node (ref "X4") (pin "16") (pinfunction "1_16") (pintype "passive"))
      (node (ref "X4") (pin "17") (pinfunction "1_17") (pintype "passive"))
      (node (ref "X4") (pin "18") (pinfunction "1_18") (pintype "passive"))
      (node (ref "X4") (pin "19") (pinfunction "1_19") (pintype "passive"))
      (node (ref "X4") (pin "2") (pinfunction "1_2") (pintype "passive"))
      (node (ref "X4") (pin "20") (pinfunction "1_20") (pintype "passive"))
      (node (ref "X4") (pin "24") (pinfunction "1_24") (pintype "passive"))
      (node (ref "X4") (pin "3") (pinfunction "1_3") (pintype "passive"))
      (node (ref "X4") (pin "6") (pinfunction "1_6") (pintype "passive"))
      (node (ref "X4") (pin "7") (pinfunction "1_7") (pintype "passive"))
    )
    (net (code "59") (name "Net-(C10-Pad1)") (class "Default")
      (node (ref "C10") (pin "1") (pinfunction "1_1") (pintype "passive"))
      (node (ref "R14") (pin "1") (pinfunction "1_1") (pintype "passive"))
      (node (ref "R15") (pin "1") (pinfunction "1_1") (pintype "passive"))
      (node (ref "R16") (pin "2") (pinfunction "2_2") (pintype "passive"))
    )
    (net (code "60") (name "Net-(C13-Pad1)") (class "Default")
      (node (ref "C13") (pin "1") (pinfunction "1_1") (pintype "passive"))
      (node (ref "R17") (pin "2") (pinfunction "2_2") (pintype "passive"))
      (node (ref "R18") (pin "1") (pinfunction "1_1") (pintype "passive"))
      (node (ref "R19") (pin "2") (pinfunction "2_2") (pintype "passive"))
    )
    (net (code "61") (name "Net-(C14-Pad1)") (class "Default")
      (node (ref "C14") (pin "1") (pinfunction "1_1") (pintype "passive"))
      (node (ref "R20") (pin "1") (pinfunction "1_1") (pintype "passive"))
      (node (ref "R21") (pin "2") (pinfunction "2_2") (pintype "passive"))
      (node (ref "R22") (pin "2") (pinfunction "2_2") (pintype "passive"))
    )
    (net (code "62") (name "Net-(C18-Pad1)") (class "Default")
      (node (ref "C18") (pin "1") (pinfunction "1_1") (pintype "passive"))
      (node (ref "R25") (pin "1") (pinfunction "1_1") (pintype "passive"))
      (node (ref "R26") (pin "2") (pinfunction "2_2") (pintype "passive"))
      (node (ref "R28") (pin "1") (pinfunction "1_1") (pintype "passive"))
    )
    (net (code "63") (name "Net-(IC2A-+IN)") (class "Default")
      (node (ref "IC2") (pin "3") (pinfunction "+IN_3") (pintype "input"))
      (node (ref "R3") (pin "2") (pinfunction "2_2") (pintype "passive"))
      (node (ref "R4") (pin "1") (pinfunction "1_1") (pintype "passive"))
    )
    (net (code "64") (name "Net-(IC2A--IN)") (class "Default")
      (node (ref "IC2") (pin "2") (pinfunction "-IN_2") (pintype "input"))
      (node (ref "P5") (pin "PA2") (pinfunction "2_PA2") (pintype "bidirectional"))
      (node (ref "R1") (pin "2") (pinfunction "2_2") (pintype "passive"))
      (node (ref "R8") (pin "1") (pinfunction "1_1") (pintype "passive"))
    )
    (net (code "65") (name "Net-(IC2A-OUT)") (class "Default")
      (node (ref "IC2") (pin "1") (pinfunction "OUT_1") (pintype "output"))
      (node (ref "R1") (pin "1") (pinfunction "1_1") (pintype "passive"))
      (node (ref "R7") (pin "2") (pinfunction "2_2") (pintype "passive"))
    )
    (net (code "66") (name "Net-(IC2B-+IN)") (class "Default")
      (node (ref "IC2") (pin "5") (pinfunction "+IN_5") (pintype "input"))
      (node (ref "R5") (pin "2") (pinfunction "2_2") (pintype "passive"))
      (node (ref "R6") (pin "1") (pinfunction "1_1") (pintype "passive"))
    )
    (net (code "67") (name "Net-(IC2B--IN)") (class "Default")
      (node (ref "IC2") (pin "6") (pinfunction "-IN_6") (pintype "input"))
      (node (ref "P5") (pin "PB2") (pinfunction "2_PB2") (pintype "bidirectional"))
      (node (ref "R11") (pin "2") (pinfunction "2_2") (pintype "passive"))
      (node (ref "R38") (pin "1") (pinfunction "1_1") (pintype "passive"))
    )
    (net (code "68") (name "Net-(IC2B-OUT)") (class "Default")
      (node (ref "IC2") (pin "7") (pinfunction "OUT_7") (pintype "output"))
      (node (ref "R10") (pin "2") (pinfunction "2_2") (pintype "passive"))
      (node (ref "R11") (pin "1") (pinfunction "1_1") (pintype "passive"))
    )
    (net (code "69") (name "Net-(IC3A-+IN)") (class "Default")
      (node (ref "C24") (pin "2") (pinfunction "2_2") (pintype "passive"))
      (node (ref "IC3") (pin "3") (pinfunction "+IN_3") (pintype "input"))
      (node (ref "R18") (pin "2") (pinfunction "2_2") (pintype "passive"))
    )
    (net (code "70") (name "Net-(IC3A--IN)") (class "Default")
      (node (ref "C11") (pin "1") (pinfunction "1_1") (pintype "passive"))
      (node (ref "IC3") (pin "2") (pinfunction "-IN_2") (pintype "input"))
      (node (ref "R15") (pin "2") (pinfunction "2_2") (pintype "passive"))
    )
    (net (code "71") (name "Net-(IC3A-OUT)") (class "Default")
      (node (ref "C11") (pin "2") (pinfunction "2_2") (pintype "passive"))
      (node (ref "IC3") (pin "1") (pinfunction "OUT_1") (pintype "output"))
      (node (ref "R13") (pin "1") (pinfunction "1_1") (pintype "passive"))
      (node (ref "R14") (pin "2") (pinfunction "2_2") (pintype "passive"))
    )
    (net (code "72") (name "Net-(IC3B-+IN)") (class "Default")
      (node (ref "C23") (pin "2") (pinfunction "2_2") (pintype "passive"))
      (node (ref "IC3") (pin "5") (pinfunction "+IN_5") (pintype "input"))
      (node (ref "R20") (pin "2") (pinfunction "2_2") (pintype "passive"))
    )
    (net (code "73") (name "Net-(IC3B--IN)") (class "Default")
      (node (ref "C16") (pin "1") (pinfunction "1_1") (pintype "passive"))
      (node (ref "IC3") (pin "6") (pinfunction "-IN_6") (pintype "input"))
      (node (ref "R25") (pin "2") (pinfunction "2_2") (pintype "passive"))
    )
    (net (code "74") (name "Net-(IC3B-OUT)") (class "Default")
      (node (ref "C16") (pin "2") (pinfunction "2_2") (pintype "passive"))
      (node (ref "IC3") (pin "7") (pinfunction "OUT_7") (pintype "output"))
      (node (ref "R27") (pin "1") (pinfunction "1_1") (pintype "passive"))
      (node (ref "R28") (pin "2") (pinfunction "2_2") (pintype "passive"))
    )
    (net (code "75") (name "Net-(P5B-3)") (class "Default")
      (node (ref "P5") (pin "PA3") (pinfunction "3_PA3") (pintype "bidirectional"))
      (node (ref "R2") (pin "1") (pinfunction "1_1") (pintype "passive"))
    )
    (net (code "76") (name "Net-(P5C-3)") (class "Default")
      (node (ref "P5") (pin "PB3") (pinfunction "3_PB3") (pintype "bidirectional"))
      (node (ref "R12") (pin "1") (pinfunction "1_1") (pintype "passive"))
    )
    (net (code "77") (name "Net-(P7B-3)") (class "Default")
      (node (ref "P7") (pin "PA3") (pinfunction "3_PA3") (pintype "bidirectional"))
      (node (ref "R13") (pin "2") (pinfunction "2_2") (pintype "passive"))
    )
    (net (code "78") (name "Net-(P7C-3)") (class "Default")
      (node (ref "P7") (pin "PB3") (pinfunction "3_PB3") (pintype "bidirectional"))
      (node (ref "R27") (pin "2") (pinfunction "2_2") (pintype "passive"))
    )
    (net (code "79") (name "Net-(Q1-D)") (class "Default")
      (node (ref "JP8") (pin "10") (pinfunction "10_10") (pintype "passive"))
      (node (ref "JP8") (pin "9") (pinfunction "9_9") (pintype "passive"))
      (node (ref "Q1") (pin "3") (pinfunction "D_3") (pintype "passive"))
    )
    (net (code "80") (name "Net-(Q2-D)") (class "Default")
      (node (ref "JP8") (pin "1") (pinfunction "1_1") (pintype "passive"))
      (node (ref "JP8") (pin "2") (pinfunction "2_2") (pintype "passive"))
      (node (ref "Q2") (pin "3") (pinfunction "D_3") (pintype "passive"))
    )
    (net (code "81") (name "Net-(R8-Pad2)") (class "Default")
      (node (ref "R8") (pin "2") (pinfunction "2_2") (pintype "passive"))
      (node (ref "SJ1") (pin "2") (pinfunction "2_2") (pintype "passive"))
    )
    (net (code "82") (name "Net-(R9-Pad2)") (class "Default")
      (node (ref "R9") (pin "2") (pinfunction "2_2") (pintype "passive"))
      (node (ref "SJ2") (pin "2") (pinfunction "2_2") (pintype "passive"))
    )
    (net (code "83") (name "Net-(R38-Pad2)") (class "Default")
      (node (ref "R38") (pin "2") (pinfunction "2_2") (pintype "passive"))
      (node (ref "SJ3") (pin "2") (pinfunction "2_2") (pintype "passive"))
    )
    (net (code "84") (name "Net-(R39-Pad2)") (class "Default")
      (node (ref "R39") (pin "2") (pinfunction "2_2") (pintype "passive"))
      (node (ref "SJ4") (pin "2") (pinfunction "2_2") (pintype "passive"))
    )
    (net (code "85") (name "Net-(SW1B-A)") (class "Default")
      (node (ref "R23") (pin "2") (pinfunction "2_2") (pintype "passive"))
      (node (ref "SW1") (pin "PL1") (pinfunction "A_PL1") (pintype "passive"))
    )
    (net (code "86") (name "Net-(SW1B-C)") (class "Default")
      (node (ref "SW1") (pin "PL2") (pinfunction "C_PL2") (pintype "passive"))
      (node (ref "SW2") (pin "PL2") (pinfunction "C_PL2") (pintype "passive"))
      (node (ref "SW3") (pin "PL2") (pinfunction "C_PL2") (pintype "passive"))
      (node (ref "SW4") (pin "PL2") (pinfunction "C_PL2") (pintype "passive"))
      (node (ref "SW5") (pin "PL2") (pinfunction "C_PL2") (pintype "passive"))
      (node (ref "SW6") (pin "PL2") (pinfunction "C_PL2") (pintype "passive"))
      (node (ref "U2") (pin "5") (pinfunction "OUT_5") (pintype "bidirectional"))
    )
    (net (code "87") (name "Net-(SW2B-A)") (class "Default")
      (node (ref "R24") (pin "2") (pinfunction "2_2") (pintype "passive"))
      (node (ref "SW2") (pin "PL1") (pinfunction "A_PL1") (pintype "passive"))
    )
    (net (code "88") (name "Net-(SW3B-A)") (class "Default")
      (node (ref "R30") (pin "2") (pinfunction "2_2") (pintype "passive"))
      (node (ref "SW3") (pin "PL1") (pinfunction "A_PL1") (pintype "passive"))
    )
    (net (code "89") (name "Net-(SW4B-A)") (class "Default")
      (node (ref "R29") (pin "2") (pinfunction "2_2") (pintype "passive"))
      (node (ref "SW4") (pin "PL1") (pinfunction "A_PL1") (pintype "passive"))
    )
    (net (code "90") (name "Net-(SW5B-A)") (class "Default")
      (node (ref "R31") (pin "2") (pinfunction "2_2") (pintype "passive"))
      (node (ref "SW5") (pin "PL1") (pinfunction "A_PL1") (pintype "passive"))
    )
    (net (code "91") (name "Net-(SW6B-A)") (class "Default")
      (node (ref "R32") (pin "2") (pinfunction "2_2") (pintype "passive"))
      (node (ref "SW6") (pin "PL1") (pinfunction "A_PL1") (pintype "passive"))
    )
    (net (code "92") (name "Net-(SW7B-A)") (class "Default")
      (node (ref "R40") (pin "2") (pinfunction "2_2") (pintype "passive"))
      (node (ref "SW7") (pin "P$A") (pinfunction "A_P$A") (pintype "passive"))
    )
    (net (code "93") (name "Net-(X4N-1)") (class "Default")
      (node (ref "R801") (pin "2") (pinfunction "2_2") (pintype "passive"))
      (node (ref "X4") (pin "21") (pinfunction "1_21") (pintype "passive"))
    )
    (net (code "94") (name "Net-(X4O-1)") (class "Default")
      (node (ref "C31") (pin "+") (pinfunction "+_+") (pintype "passive"))
      (node (ref "X4") (pin "22") (pinfunction "1_22") (pintype "passive"))
    )
    (net (code "95") (name "unconnected-(ANG2-Pad6)") (class "Default")
      (node (ref "ANG2") (pin "6") (pinfunction "6_6") (pintype "passive"))
    )
    (net (code "96") (name "unconnected-(OUT_L-4-PadP$2)") (class "Default")
      (node (ref "OUT_L") (pin "P$2") (pinfunction "4_P$2") (pintype "passive"))
    )
    (net (code "97") (name "unconnected-(OUT_R-4-PadP$2)") (class "Default")
      (node (ref "OUT_R") (pin "P$2") (pinfunction "4_P$2") (pintype "passive"))
    )
    (net (code "98") (name "unconnected-(X4G-1-Pad15)") (class "Default")
      (node (ref "X4") (pin "15") (pinfunction "1_15") (pintype "passive"))
    )
    (net (code "99") (name "unconnected-(X4S-1-Pad4)") (class "Default")
      (node (ref "X4") (pin "4") (pinfunction "1_4") (pintype "passive"))
    )
  )
)
